# alfred_comm.net
KiCad netlist of a schematic drawn in EAGLE
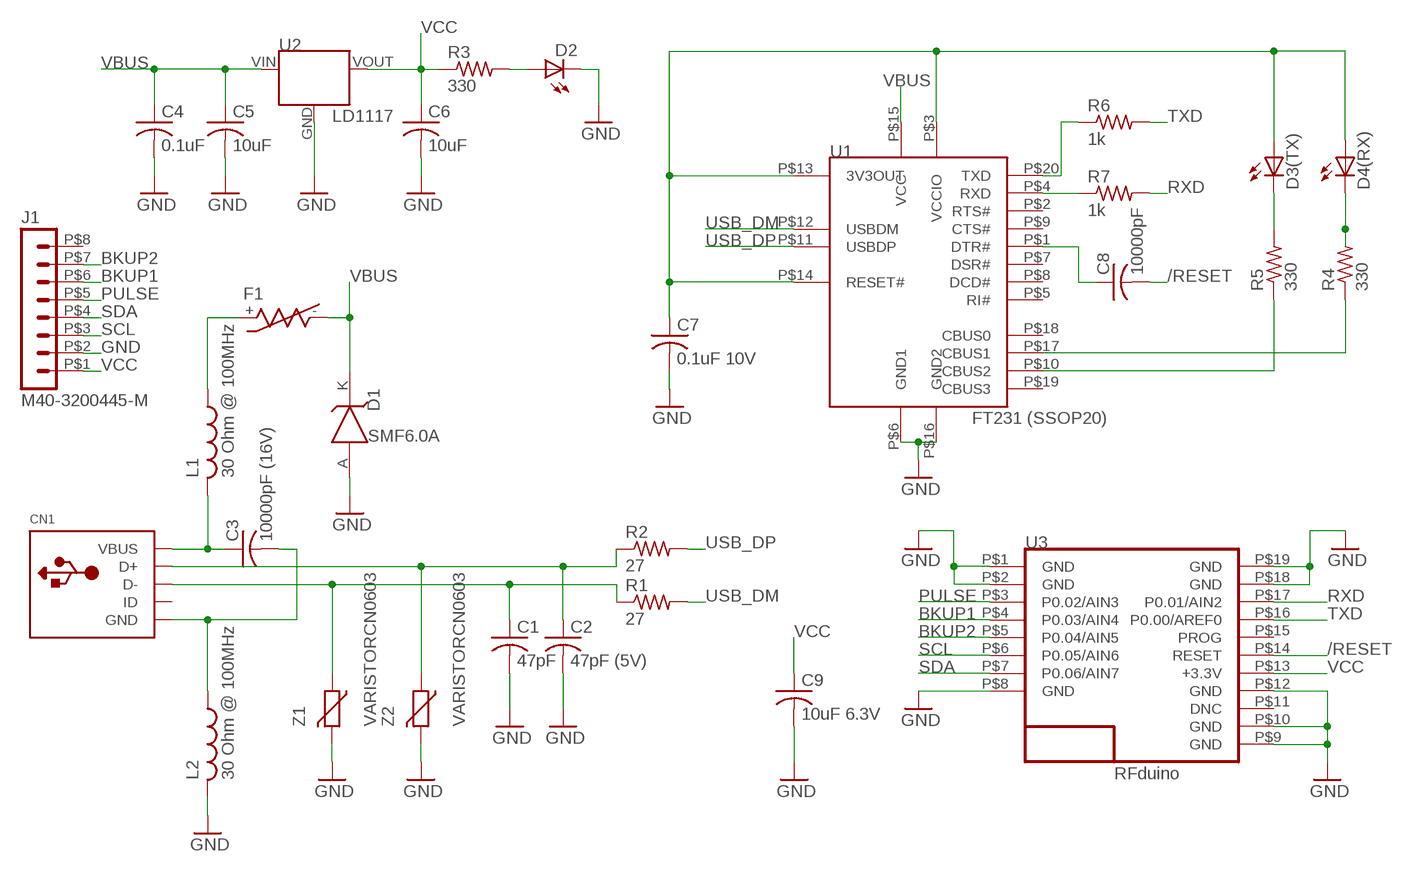
[diagram p0: schematic, sheet 1]

(export (version "E")
  (design (tool "Eeschema 10.0.6"))
  (components
    (comp (ref "C1")
      (value "47pF")
      (footprint "eagle-import:C0603")
      (libsource (lib "eagle-import") (part "C-USC0603"))
    )
    (comp (ref "C2")
      (value "47pF (5V)")
      (footprint "eagle-import:C0603")
      (libsource (lib "eagle-import") (part "C-USC0603"))
    )
    (comp (ref "C3")
      (value "10000pF (16V)")
      (footprint "eagle-import:C0603")
      (libsource (lib "eagle-import") (part "C-USC0603"))
    )
    (comp (ref "C4")
      (value "0.1uF")
      (footprint "eagle-import:C0603")
      (libsource (lib "eagle-import") (part "C-USC0603"))
    )
    (comp (ref "C5")
      (value "10uF")
      (footprint "eagle-import:C0603")
      (libsource (lib "eagle-import") (part "C-USC0603"))
    )
    (comp (ref "C6")
      (value "10uF")
      (footprint "eagle-import:C0603")
      (libsource (lib "eagle-import") (part "C-USC0603"))
    )
    (comp (ref "C7")
      (value "0.1uF 10V")
      (footprint "eagle-import:C0603")
      (libsource (lib "eagle-import") (part "C-USC0603"))
    )
    (comp (ref "C8")
      (value "10000pF")
      (footprint "eagle-import:C0603")
      (libsource (lib "eagle-import") (part "C-USC0603"))
    )
    (comp (ref "C9")
      (value "10uF 6.3V")
      (footprint "eagle-import:C0603")
      (libsource (lib "eagle-import") (part "C-USC0603"))
    )
    (comp (ref "CN1")
      (value "USBMINIB")
      (footprint "eagle-import:USB-MINIB")
      (libsource (lib "eagle-import") (part "USBMINIB"))
    )
    (comp (ref "D1")
      (value "SMF6.0A")
      (footprint "eagle-import:SOD-123F")
      (libsource (lib "eagle-import") (part "SMF6.0A"))
    )
    (comp (ref "D2")
      (value "LEDCHIPLED_0603")
      (footprint "eagle-import:CHIPLED_0603")
      (libsource (lib "eagle-import") (part "LEDCHIPLED_0603"))
    )
    (comp (ref "D3(TX)")
      (value "LEDCHIPLED_0603")
      (footprint "eagle-import:CHIPLED_0603")
      (libsource (lib "eagle-import") (part "LEDCHIPLED_0603"))
    )
    (comp (ref "D4(RX)")
      (value "LEDCHIPLED_0603")
      (footprint "eagle-import:CHIPLED_0603")
      (libsource (lib "eagle-import") (part "LEDCHIPLED_0603"))
    )
    (comp (ref "F1")
      (value "MF-MSMF050")
      (footprint "eagle-import:BOURNS-STYLE1")
      (libsource (lib "eagle-import") (part "MF-MSMF050"))
    )
    (comp (ref "J1")
      (value "M40-3200445-M")
      (footprint "eagle-import:8-PO-M")
      (libsource (lib "eagle-import") (part "M40-3200445-M"))
    )
    (comp (ref "L1")
      (value "30 Ohm @ 100MHz")
      (footprint "eagle-import:L0603")
      (libsource (lib "eagle-import") (part "L-US0603"))
    )
    (comp (ref "L2")
      (value "30 Ohm @ 100MHz")
      (footprint "eagle-import:L0603")
      (libsource (lib "eagle-import") (part "L-US0603"))
    )
    (comp (ref "R1")
      (value "27")
      (footprint "eagle-import:R0603")
      (libsource (lib "eagle-import") (part "R-US_R0603"))
    )
    (comp (ref "R2")
      (value "27")
      (footprint "eagle-import:R0603")
      (libsource (lib "eagle-import") (part "R-US_R0603"))
    )
    (comp (ref "R3")
      (value "330")
      (footprint "eagle-import:R0603")
      (libsource (lib "eagle-import") (part "R-US_R0603"))
    )
    (comp (ref "R4")
      (value "330")
      (footprint "eagle-import:R0603")
      (libsource (lib "eagle-import") (part "R-US_R0603"))
    )
    (comp (ref "R5")
      (value "330")
      (footprint "eagle-import:R0603")
      (libsource (lib "eagle-import") (part "R-US_R0603"))
    )
    (comp (ref "R6")
      (value "1k")
      (footprint "eagle-import:R0603")
      (libsource (lib "eagle-import") (part "R-US_R0603"))
    )
    (comp (ref "R7")
      (value "1k")
      (footprint "eagle-import:R0603")
      (libsource (lib "eagle-import") (part "R-US_R0603"))
    )
    (comp (ref "U1")
      (value "FT231")
      (footprint "eagle-import:SSOP20")
      (libsource (lib "eagle-import") (part "FT231"))
    )
    (comp (ref "U2")
      (value "LD1117-SOT-223")
      (footprint "eagle-import:SOT223")
      (libsource (lib "eagle-import") (part "LD1117-SOT-223"))
    )
    (comp (ref "U3")
      (value "RFD22301")
      (footprint "eagle-import:RFD21733")
      (libsource (lib "eagle-import") (part "RFD22301"))
    )
    (comp (ref "Z1")
      (value "VARISTORCN0603")
      (footprint "eagle-import:CT_CN0603")
      (libsource (lib "eagle-import") (part "VARISTORCN0603"))
    )
    (comp (ref "Z2")
      (value "VARISTORCN0603")
      (footprint "eagle-import:CT_CN0603")
      (libsource (lib "eagle-import") (part "VARISTORCN0603"))
    )
  )
  (nets
    (net (code "1") (name "/BKUP1") (class "Default")
      (node (ref "J1") (pin "P$6") (pinfunction "6_P$6") (pintype "passive"))
      (node (ref "U3") (pin "P$4") (pinfunction "P0.03/AIN4_P$4") (pintype "bidirectional"))
    )
    (net (code "2") (name "/BKUP2") (class "Default")
      (node (ref "J1") (pin "P$7") (pinfunction "7_P$7") (pintype "passive"))
      (node (ref "U3") (pin "P$5") (pinfunction "P0.04/AIN5_P$5") (pintype "bidirectional"))
    )
    (net (code "3") (name "/PULSE") (class "Default")
      (node (ref "J1") (pin "P$5") (pinfunction "5_P$5") (pintype "passive"))
      (node (ref "U3") (pin "P$3") (pinfunction "P0.02/AIN3_P$3") (pintype "bidirectional"))
    )
    (net (code "4") (name "/RXD") (class "Default")
      (node (ref "R7") (pin "2") (pinfunction "2_2") (pintype "passive"))
      (node (ref "U3") (pin "P$17") (pinfunction "P0.01/AIN2_P$17") (pintype "bidirectional"))
    )
    (net (code "5") (name "/SCL") (class "Default")
      (node (ref "J1") (pin "P$3") (pinfunction "3_P$3") (pintype "passive"))
      (node (ref "U3") (pin "P$6") (pinfunction "P0.05/AIN6_P$6") (pintype "bidirectional"))
    )
    (net (code "6") (name "/SDA") (class "Default")
      (node (ref "J1") (pin "P$4") (pinfunction "4_P$4") (pintype "passive"))
      (node (ref "U3") (pin "P$7") (pinfunction "P0.06/AIN7_P$7") (pintype "bidirectional"))
    )
    (net (code "7") (name "/TXD") (class "Default")
      (node (ref "R6") (pin "2") (pinfunction "2_2") (pintype "passive"))
      (node (ref "U3") (pin "P$16") (pinfunction "P0.00/AREF0_P$16") (pintype "bidirectional"))
    )
    (net (code "8") (name "/USB_DM") (class "Default")
      (node (ref "R1") (pin "2") (pinfunction "2_2") (pintype "passive"))
      (node (ref "U1") (pin "P$12") (pinfunction "USBDM_P$12") (pintype "bidirectional"))
    )
    (net (code "9") (name "/USB_DP") (class "Default")
      (node (ref "R2") (pin "2") (pinfunction "2_2") (pintype "passive"))
      (node (ref "U1") (pin "P$11") (pinfunction "USBDP_P$11") (pintype "bidirectional"))
    )
    (net (code "10") (name "/VBUS") (class "Default")
      (node (ref "C4") (pin "1") (pinfunction "1_1") (pintype "passive"))
      (node (ref "C5") (pin "1") (pinfunction "1_1") (pintype "passive"))
      (node (ref "D1") (pin "K") (pinfunction "K_K") (pintype "bidirectional"))
      (node (ref "F1") (pin "-") (pinfunction "P$2_-") (pintype "bidirectional"))
      (node (ref "U1") (pin "P$15") (pinfunction "VCC_P$15") (pintype "bidirectional"))
      (node (ref "U2") (pin "VIN") (pinfunction "IN_VIN") (pintype "bidirectional"))
    )
    (net (code "11") (name "/VCC") (class "Default")
      (node (ref "C6") (pin "1") (pinfunction "1_1") (pintype "passive"))
      (node (ref "C9") (pin "1") (pinfunction "1_1") (pintype "passive"))
      (node (ref "J1") (pin "P$1") (pinfunction "1_P$1") (pintype "passive"))
      (node (ref "R3") (pin "1") (pinfunction "1_1") (pintype "passive"))
      (node (ref "U2") (pin "VOUT") (pinfunction "OUT_VOUT") (pintype "bidirectional"))
      (node (ref "U3") (pin "P$13") (pinfunction "+3.3V_P$13") (pintype "bidirectional"))
    )
    (net (code "12") (name "/{slash}RESET") (class "Default")
      (node (ref "C8") (pin "2") (pinfunction "2_2") (pintype "passive"))
      (node (ref "U3") (pin "P$14") (pinfunction "RESET_P$14") (pintype "bidirectional"))
    )
    (net (code "13") (name "GND") (class "Default")
      (node (ref "C1") (pin "2") (pinfunction "2_2") (pintype "passive"))
      (node (ref "C2") (pin "2") (pinfunction "2_2") (pintype "passive"))
      (node (ref "C4") (pin "2") (pinfunction "2_2") (pintype "passive"))
      (node (ref "C5") (pin "2") (pinfunction "2_2") (pintype "passive"))
      (node (ref "C6") (pin "2") (pinfunction "2_2") (pintype "passive"))
      (node (ref "C7") (pin "2") (pinfunction "2_2") (pintype "passive"))
      (node (ref "C9") (pin "2") (pinfunction "2_2") (pintype "passive"))
      (node (ref "D1") (pin "A") (pinfunction "A_A") (pintype "bidirectional"))
      (node (ref "D2") (pin "C") (pinfunction "C_C") (pintype "passive"))
      (node (ref "J1") (pin "P$2") (pinfunction "2_P$2") (pintype "passive"))
      (node (ref "L2") (pin "2") (pinfunction "2_2") (pintype "passive"))
      (node (ref "U1") (pin "P$16") (pinfunction "GND2_P$16") (pintype "bidirectional"))
      (node (ref "U1") (pin "P$6") (pinfunction "GND1_P$6") (pintype "bidirectional"))
      (node (ref "U2") (pin "GND") (pinfunction "GND_GND") (pintype "bidirectional"))
      (node (ref "U3") (pin "P$1") (pinfunction "GND_P$1") (pintype "bidirectional"))
      (node (ref "U3") (pin "P$10") (pinfunction "GND_P$10") (pintype "bidirectional"))
      (node (ref "U3") (pin "P$12") (pinfunction "GND_P$12") (pintype "bidirectional"))
      (node (ref "U3") (pin "P$18") (pinfunction "GND_P$18") (pintype "bidirectional"))
      (node (ref "U3") (pin "P$19") (pinfunction "GND_P$19") (pintype "bidirectional"))
      (node (ref "U3") (pin "P$2") (pinfunction "GND_P$2") (pintype "bidirectional"))
      (node (ref "U3") (pin "P$8") (pinfunction "GND_P$8") (pintype "bidirectional"))
      (node (ref "U3") (pin "P$9") (pinfunction "GND_P$9") (pintype "bidirectional"))
      (node (ref "Z1") (pin "2") (pinfunction "2_2") (pintype "passive"))
      (node (ref "Z2") (pin "2") (pinfunction "2_2") (pintype "passive"))
    )
    (net (code "14") (name "Net-(C1-Pad1)") (class "Default")
      (node (ref "C1") (pin "1") (pinfunction "1_1") (pintype "passive"))
      (node (ref "CN1") (pin "D-") (pinfunction "D-_D-") (pintype "bidirectional"))
      (node (ref "R1") (pin "1") (pinfunction "1_1") (pintype "passive"))
      (node (ref "Z1") (pin "1") (pinfunction "1_1") (pintype "passive"))
    )
    (net (code "15") (name "Net-(C2-Pad1)") (class "Default")
      (node (ref "C2") (pin "1") (pinfunction "1_1") (pintype "passive"))
      (node (ref "CN1") (pin "D+") (pinfunction "D+_D+") (pintype "bidirectional"))
      (node (ref "R2") (pin "1") (pinfunction "1_1") (pintype "passive"))
      (node (ref "Z2") (pin "1") (pinfunction "1_1") (pintype "passive"))
    )
    (net (code "16") (name "Net-(C3-Pad1)") (class "Default")
      (node (ref "C3") (pin "1") (pinfunction "1_1") (pintype "passive"))
      (node (ref "CN1") (pin "VBUS") (pinfunction "VBUS_VBUS") (pintype "power_in"))
      (node (ref "L1") (pin "2") (pinfunction "2_2") (pintype "passive"))
    )
    (net (code "17") (name "Net-(C3-Pad2)") (class "Default")
      (node (ref "C3") (pin "2") (pinfunction "2_2") (pintype "passive"))
      (node (ref "CN1") (pin "GND") (pinfunction "GND_GND") (pintype "power_in"))
      (node (ref "L2") (pin "1") (pinfunction "1_1") (pintype "passive"))
    )
    (net (code "18") (name "Net-(D2-PadA)") (class "Default")
      (node (ref "D2") (pin "A") (pinfunction "A_A") (pintype "passive"))
      (node (ref "R3") (pin "2") (pinfunction "2_2") (pintype "passive"))
    )
    (net (code "19") (name "Net-(D3(TX)-PadC)") (class "Default")
      (node (ref "D3(TX)") (pin "C") (pinfunction "C_C") (pintype "passive"))
      (node (ref "R5") (pin "2") (pinfunction "2_2") (pintype "passive"))
    )
    (net (code "20") (name "Net-(D4(RX)-PadC)") (class "Default")
      (node (ref "D4(RX)") (pin "C") (pinfunction "C_C") (pintype "passive"))
      (node (ref "R4") (pin "2") (pinfunction "2_2") (pintype "passive"))
    )
    (net (code "21") (name "Net-(F1-P$1)") (class "Default")
      (node (ref "F1") (pin "+") (pinfunction "P$1_+") (pintype "bidirectional"))
      (node (ref "L1") (pin "1") (pinfunction "1_1") (pintype "passive"))
    )
    (net (code "22") (name "Net-(U1-3V3OUT)") (class "Default")
      (node (ref "C7") (pin "1") (pinfunction "1_1") (pintype "passive"))
      (node (ref "D3(TX)") (pin "A") (pinfunction "A_A") (pintype "passive"))
      (node (ref "D4(RX)") (pin "A") (pinfunction "A_A") (pintype "passive"))
      (node (ref "U1") (pin "P$13") (pinfunction "3V3OUT_P$13") (pintype "bidirectional"))
      (node (ref "U1") (pin "P$14") (pinfunction "RESET#_P$14") (pintype "bidirectional"))
      (node (ref "U1") (pin "P$3") (pinfunction "VCCIO_P$3") (pintype "bidirectional"))
    )
    (net (code "23") (name "Net-(U1-CBUS1)") (class "Default")
      (node (ref "R4") (pin "1") (pinfunction "1_1") (pintype "passive"))
      (node (ref "U1") (pin "P$17") (pinfunction "CBUS1_P$17") (pintype "bidirectional"))
    )
    (net (code "24") (name "Net-(U1-CBUS2)") (class "Default")
      (node (ref "R5") (pin "1") (pinfunction "1_1") (pintype "passive"))
      (node (ref "U1") (pin "P$10") (pinfunction "CBUS2_P$10") (pintype "bidirectional"))
    )
    (net (code "25") (name "Net-(U1-DTR#)") (class "Default")
      (node (ref "C8") (pin "1") (pinfunction "1_1") (pintype "passive"))
      (node (ref "U1") (pin "P$1") (pinfunction "DTR#_P$1") (pintype "bidirectional"))
    )
    (net (code "26") (name "Net-(U1-RXD)") (class "Default")
      (node (ref "R7") (pin "1") (pinfunction "1_1") (pintype "passive"))
      (node (ref "U1") (pin "P$4") (pinfunction "RXD_P$4") (pintype "bidirectional"))
    )
    (net (code "27") (name "Net-(U1-TXD)") (class "Default")
      (node (ref "R6") (pin "1") (pinfunction "1_1") (pintype "passive"))
      (node (ref "U1") (pin "P$20") (pinfunction "TXD_P$20") (pintype "bidirectional"))
    )
    (net (code "28") (name "unconnected-(CN1-PadID)") (class "Default")
      (node (ref "CN1") (pin "ID") (pinfunction "ID_ID") (pintype "bidirectional"))
    )
    (net (code "29") (name "unconnected-(J1-8-PadP$8)") (class "Default")
      (node (ref "J1") (pin "P$8") (pinfunction "8_P$8") (pintype "passive"))
    )
    (net (code "30") (name "unconnected-(U1-CBUS0-PadP$18)") (class "Default")
      (node (ref "U1") (pin "P$18") (pinfunction "CBUS0_P$18") (pintype "bidirectional"))
    )
    (net (code "31") (name "unconnected-(U1-CBUS3-PadP$19)") (class "Default")
      (node (ref "U1") (pin "P$19") (pinfunction "CBUS3_P$19") (pintype "bidirectional"))
    )
    (net (code "32") (name "unconnected-(U1-CTS#-PadP$9)") (class "Default")
      (node (ref "U1") (pin "P$9") (pinfunction "CTS#_P$9") (pintype "bidirectional"))
    )
    (net (code "33") (name "unconnected-(U1-DCD#-PadP$8)") (class "Default")
      (node (ref "U1") (pin "P$8") (pinfunction "DCD#_P$8") (pintype "bidirectional"))
    )
    (net (code "34") (name "unconnected-(U1-DSR#-PadP$7)") (class "Default")
      (node (ref "U1") (pin "P$7") (pinfunction "DSR#_P$7") (pintype "bidirectional"))
    )
    (net (code "35") (name "unconnected-(U1-RI#-PadP$5)") (class "Default")
      (node (ref "U1") (pin "P$5") (pinfunction "RI#_P$5") (pintype "bidirectional"))
    )
    (net (code "36") (name "unconnected-(U1-RTS#-PadP$2)") (class "Default")
      (node (ref "U1") (pin "P$2") (pinfunction "RTS#_P$2") (pintype "bidirectional"))
    )
    (net (code "37") (name "unconnected-(U3-DNC-PadP$11)") (class "Default")
      (node (ref "U3") (pin "P$11") (pinfunction "DNC_P$11") (pintype "bidirectional"))
    )
    (net (code "38") (name "unconnected-(U3-PROG-PadP$15)") (class "Default")
      (node (ref "U3") (pin "P$15") (pinfunction "PROG_P$15") (pintype "bidirectional"))
    )
  )
)
